# 2_Unextended55_matrix.net
KiCad netlist of a schematic drawn in Altium Designer
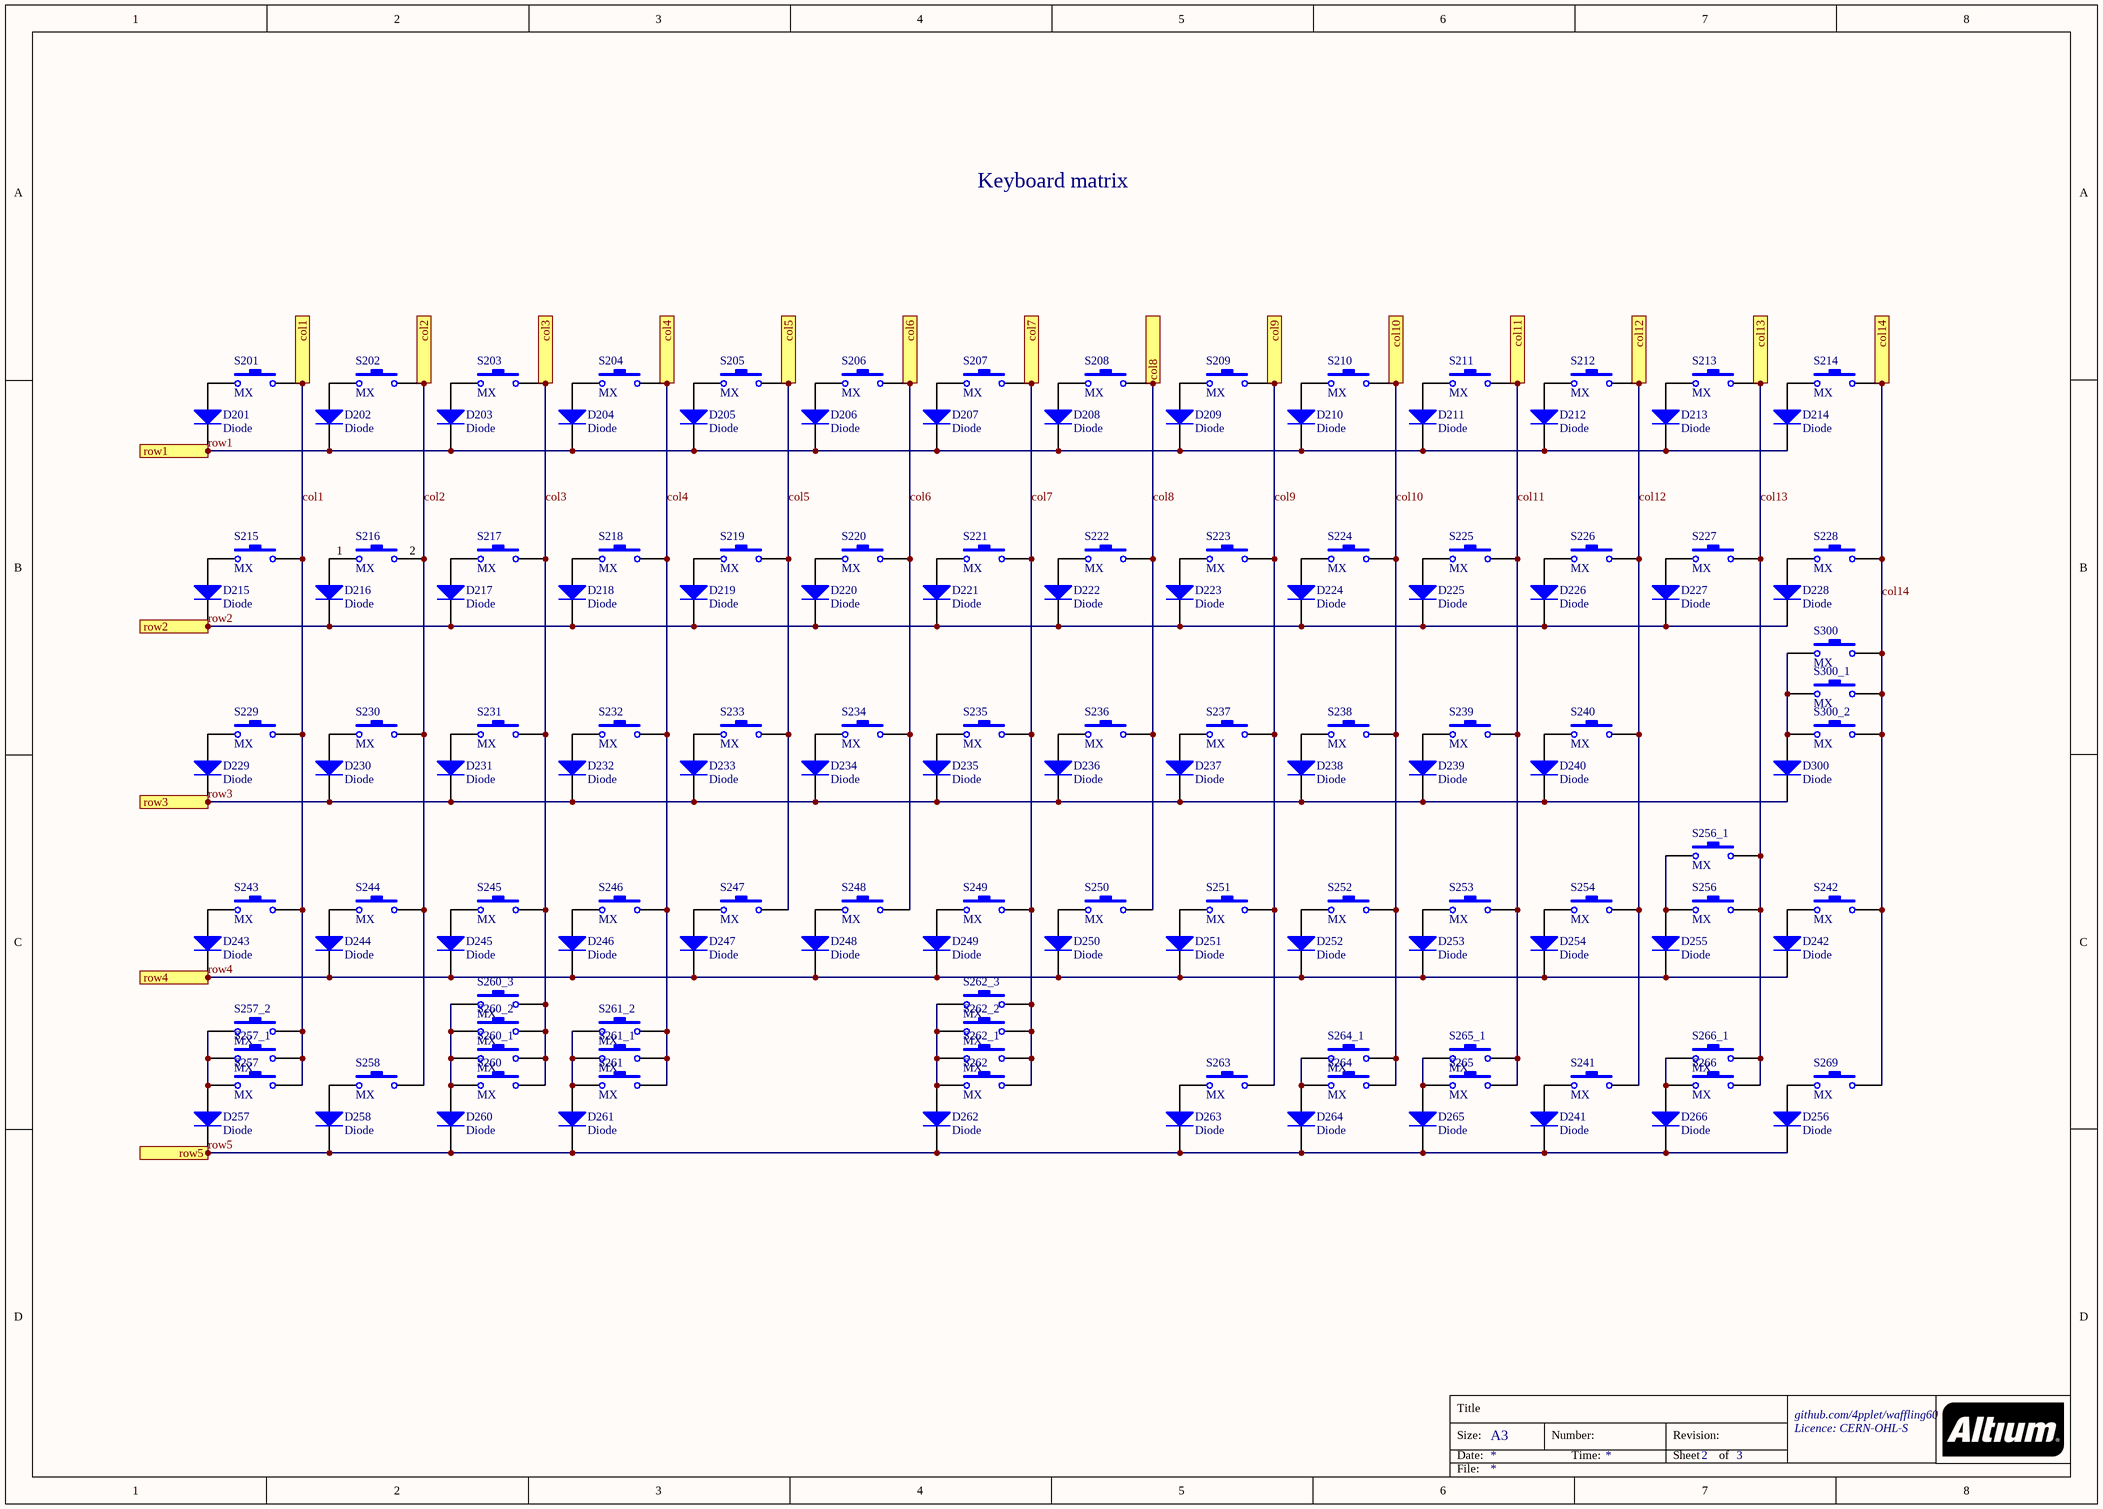
[diagram p0: 2_Unextended55_matrix.SchDoc]

(export (version "E")
  (design (tool "Eeschema 10.0.6"))
  (components
    (comp (ref "D201")
      (value "Diode")
      (footprint "SOD-123")
      (description "Default Diode")
      (fields (field (name "LCSC PART #") "C81598") (field (name "MRF.PART") "1N4148W"))
      (libsource (lib "Miscellaneous Devices") (part "Diode"))
    )
    (comp (ref "D202")
      (value "Diode")
      (footprint "SOD-123")
      (description "Default Diode")
      (fields (field (name "LCSC PART #") "C81598") (field (name "MRF.PART") "1N4148W"))
      (libsource (lib "Miscellaneous Devices") (part "Diode"))
    )
    (comp (ref "D203")
      (value "Diode")
      (footprint "SOD-123")
      (description "Default Diode")
      (fields (field (name "LCSC PART #") "C81598") (field (name "MRF.PART") "1N4148W"))
      (libsource (lib "Miscellaneous Devices") (part "Diode"))
    )
    (comp (ref "D204")
      (value "Diode")
      (footprint "SOD-123")
      (description "Default Diode")
      (fields (field (name "LCSC PART #") "C81598") (field (name "MRF.PART") "1N4148W"))
      (libsource (lib "Miscellaneous Devices") (part "Diode"))
    )
    (comp (ref "D205")
      (value "Diode")
      (footprint "SOD-123")
      (description "Default Diode")
      (fields (field (name "LCSC PART #") "C81598") (field (name "MRF.PART") "1N4148W"))
      (libsource (lib "Miscellaneous Devices") (part "Diode"))
    )
    (comp (ref "D206")
      (value "Diode")
      (footprint "SOD-123")
      (description "Default Diode")
      (fields (field (name "LCSC PART #") "C81598") (field (name "MRF.PART") "1N4148W"))
      (libsource (lib "Miscellaneous Devices") (part "Diode"))
    )
    (comp (ref "D207")
      (value "Diode")
      (footprint "SOD-123")
      (description "Default Diode")
      (fields (field (name "LCSC PART #") "C81598") (field (name "MRF.PART") "1N4148W"))
      (libsource (lib "Miscellaneous Devices") (part "Diode"))
    )
    (comp (ref "D208")
      (value "Diode")
      (footprint "SOD-123")
      (description "Default Diode")
      (fields (field (name "LCSC PART #") "C81598") (field (name "MRF.PART") "1N4148W"))
      (libsource (lib "Miscellaneous Devices") (part "Diode"))
    )
    (comp (ref "D209")
      (value "Diode")
      (footprint "SOD-123")
      (description "Default Diode")
      (fields (field (name "LCSC PART #") "C81598") (field (name "MRF.PART") "1N4148W"))
      (libsource (lib "Miscellaneous Devices") (part "Diode"))
    )
    (comp (ref "D210")
      (value "Diode")
      (footprint "SOD-123")
      (description "Default Diode")
      (fields (field (name "LCSC PART #") "C81598") (field (name "MRF.PART") "1N4148W"))
      (libsource (lib "Miscellaneous Devices") (part "Diode"))
    )
    (comp (ref "D211")
      (value "Diode")
      (footprint "SOD-123")
      (description "Default Diode")
      (fields (field (name "LCSC PART #") "C81598") (field (name "MRF.PART") "1N4148W"))
      (libsource (lib "Miscellaneous Devices") (part "Diode"))
    )
    (comp (ref "D212")
      (value "Diode")
      (footprint "SOD-123")
      (description "Default Diode")
      (fields (field (name "LCSC PART #") "C81598") (field (name "MRF.PART") "1N4148W"))
      (libsource (lib "Miscellaneous Devices") (part "Diode"))
    )
    (comp (ref "D213")
      (value "Diode")
      (footprint "SOD-123")
      (description "Default Diode")
      (fields (field (name "LCSC PART #") "C81598") (field (name "MRF.PART") "1N4148W"))
      (libsource (lib "Miscellaneous Devices") (part "Diode"))
    )
    (comp (ref "D214")
      (value "Diode")
      (footprint "SOD-123")
      (description "Default Diode")
      (fields (field (name "LCSC PART #") "C81598") (field (name "MRF.PART") "1N4148W"))
      (libsource (lib "Miscellaneous Devices") (part "Diode"))
    )
    (comp (ref "D215")
      (value "Diode")
      (footprint "SOD-123")
      (description "Default Diode")
      (fields (field (name "LCSC PART #") "C81598") (field (name "MRF.PART") "1N4148W"))
      (libsource (lib "Miscellaneous Devices") (part "Diode"))
    )
    (comp (ref "D216")
      (value "Diode")
      (footprint "SOD-123")
      (description "Default Diode")
      (fields (field (name "LCSC PART #") "C81598") (field (name "MRF.PART") "1N4148W"))
      (libsource (lib "Miscellaneous Devices") (part "Diode"))
    )
    (comp (ref "D217")
      (value "Diode")
      (footprint "SOD-123")
      (description "Default Diode")
      (fields (field (name "LCSC PART #") "C81598") (field (name "MRF.PART") "1N4148W"))
      (libsource (lib "Miscellaneous Devices") (part "Diode"))
    )
    (comp (ref "D218")
      (value "Diode")
      (footprint "SOD-123")
      (description "Default Diode")
      (fields (field (name "LCSC PART #") "C81598") (field (name "MRF.PART") "1N4148W"))
      (libsource (lib "Miscellaneous Devices") (part "Diode"))
    )
    (comp (ref "D219")
      (value "Diode")
      (footprint "SOD-123")
      (description "Default Diode")
      (fields (field (name "LCSC PART #") "C81598") (field (name "MRF.PART") "1N4148W"))
      (libsource (lib "Miscellaneous Devices") (part "Diode"))
    )
    (comp (ref "D220")
      (value "Diode")
      (footprint "SOD-123")
      (description "Default Diode")
      (fields (field (name "LCSC PART #") "C81598") (field (name "MRF.PART") "1N4148W"))
      (libsource (lib "Miscellaneous Devices") (part "Diode"))
    )
    (comp (ref "D221")
      (value "Diode")
      (footprint "SOD-123")
      (description "Default Diode")
      (fields (field (name "LCSC PART #") "C81598") (field (name "MRF.PART") "1N4148W"))
      (libsource (lib "Miscellaneous Devices") (part "Diode"))
    )
    (comp (ref "D222")
      (value "Diode")
      (footprint "SOD-123")
      (description "Default Diode")
      (fields (field (name "LCSC PART #") "C81598") (field (name "MRF.PART") "1N4148W"))
      (libsource (lib "Miscellaneous Devices") (part "Diode"))
    )
    (comp (ref "D223")
      (value "Diode")
      (footprint "SOD-123")
      (description "Default Diode")
      (fields (field (name "LCSC PART #") "C81598") (field (name "MRF.PART") "1N4148W"))
      (libsource (lib "Miscellaneous Devices") (part "Diode"))
    )
    (comp (ref "D224")
      (value "Diode")
      (footprint "SOD-123")
      (description "Default Diode")
      (fields (field (name "LCSC PART #") "C81598") (field (name "MRF.PART") "1N4148W"))
      (libsource (lib "Miscellaneous Devices") (part "Diode"))
    )
    (comp (ref "D225")
      (value "Diode")
      (footprint "SOD-123")
      (description "Default Diode")
      (fields (field (name "LCSC PART #") "C81598") (field (name "MRF.PART") "1N4148W"))
      (libsource (lib "Miscellaneous Devices") (part "Diode"))
    )
    (comp (ref "D226")
      (value "Diode")
      (footprint "SOD-123")
      (description "Default Diode")
      (fields (field (name "LCSC PART #") "C81598") (field (name "MRF.PART") "1N4148W"))
      (libsource (lib "Miscellaneous Devices") (part "Diode"))
    )
    (comp (ref "D227")
      (value "Diode")
      (footprint "SOD-123")
      (description "Default Diode")
      (fields (field (name "LCSC PART #") "C81598") (field (name "MRF.PART") "1N4148W"))
      (libsource (lib "Miscellaneous Devices") (part "Diode"))
    )
    (comp (ref "D228")
      (value "Diode")
      (footprint "SOD-123")
      (description "Default Diode")
      (fields (field (name "LCSC PART #") "C81598") (field (name "MRF.PART") "1N4148W"))
      (libsource (lib "Miscellaneous Devices") (part "Diode"))
    )
    (comp (ref "D229")
      (value "Diode")
      (footprint "SOD-123")
      (description "Default Diode")
      (fields (field (name "LCSC PART #") "C81598") (field (name "MRF.PART") "1N4148W"))
      (libsource (lib "Miscellaneous Devices") (part "Diode"))
    )
    (comp (ref "D230")
      (value "Diode")
      (footprint "SOD-123")
      (description "Default Diode")
      (fields (field (name "LCSC PART #") "C81598") (field (name "MRF.PART") "1N4148W"))
      (libsource (lib "Miscellaneous Devices") (part "Diode"))
    )
    (comp (ref "D231")
      (value "Diode")
      (footprint "SOD-123")
      (description "Default Diode")
      (fields (field (name "LCSC PART #") "C81598") (field (name "MRF.PART") "1N4148W"))
      (libsource (lib "Miscellaneous Devices") (part "Diode"))
    )
    (comp (ref "D232")
      (value "Diode")
      (footprint "SOD-123")
      (description "Default Diode")
      (fields (field (name "LCSC PART #") "C81598") (field (name "MRF.PART") "1N4148W"))
      (libsource (lib "Miscellaneous Devices") (part "Diode"))
    )
    (comp (ref "D233")
      (value "Diode")
      (footprint "SOD-123")
      (description "Default Diode")
      (fields (field (name "LCSC PART #") "C81598") (field (name "MRF.PART") "1N4148W"))
      (libsource (lib "Miscellaneous Devices") (part "Diode"))
    )
    (comp (ref "D234")
      (value "Diode")
      (footprint "SOD-123")
      (description "Default Diode")
      (fields (field (name "LCSC PART #") "C81598") (field (name "MRF.PART") "1N4148W"))
      (libsource (lib "Miscellaneous Devices") (part "Diode"))
    )
    (comp (ref "D235")
      (value "Diode")
      (footprint "SOD-123")
      (description "Default Diode")
      (fields (field (name "LCSC PART #") "C81598") (field (name "MRF.PART") "1N4148W"))
      (libsource (lib "Miscellaneous Devices") (part "Diode"))
    )
    (comp (ref "D236")
      (value "Diode")
      (footprint "SOD-123")
      (description "Default Diode")
      (fields (field (name "LCSC PART #") "C81598") (field (name "MRF.PART") "1N4148W"))
      (libsource (lib "Miscellaneous Devices") (part "Diode"))
    )
    (comp (ref "D237")
      (value "Diode")
      (footprint "SOD-123")
      (description "Default Diode")
      (fields (field (name "LCSC PART #") "C81598") (field (name "MRF.PART") "1N4148W"))
      (libsource (lib "Miscellaneous Devices") (part "Diode"))
    )
    (comp (ref "D238")
      (value "Diode")
      (footprint "SOD-123")
      (description "Default Diode")
      (fields (field (name "LCSC PART #") "C81598") (field (name "MRF.PART") "1N4148W"))
      (libsource (lib "Miscellaneous Devices") (part "Diode"))
    )
    (comp (ref "D239")
      (value "Diode")
      (footprint "SOD-123")
      (description "Default Diode")
      (fields (field (name "LCSC PART #") "C81598") (field (name "MRF.PART") "1N4148W"))
      (libsource (lib "Miscellaneous Devices") (part "Diode"))
    )
    (comp (ref "D240")
      (value "Diode")
      (footprint "SOD-123")
      (description "Default Diode")
      (fields (field (name "LCSC PART #") "C81598") (field (name "MRF.PART") "1N4148W"))
      (libsource (lib "Miscellaneous Devices") (part "Diode"))
    )
    (comp (ref "D241")
      (value "Diode")
      (footprint "SOD-123")
      (description "Default Diode")
      (fields (field (name "LCSC PART #") "C81598") (field (name "MRF.PART") "1N4148W"))
      (libsource (lib "Miscellaneous Devices") (part "Diode"))
    )
    (comp (ref "D242")
      (value "Diode")
      (footprint "SOD-123")
      (description "Default Diode")
      (fields (field (name "LCSC PART #") "C81598") (field (name "MRF.PART") "1N4148W"))
      (libsource (lib "Miscellaneous Devices") (part "Diode"))
    )
    (comp (ref "D243")
      (value "Diode")
      (footprint "SOD-123")
      (description "Default Diode")
      (fields (field (name "LCSC PART #") "C81598") (field (name "MRF.PART") "1N4148W"))
      (libsource (lib "Miscellaneous Devices") (part "Diode"))
    )
    (comp (ref "D244")
      (value "Diode")
      (footprint "SOD-123")
      (description "Default Diode")
      (fields (field (name "LCSC PART #") "C81598") (field (name "MRF.PART") "1N4148W"))
      (libsource (lib "Miscellaneous Devices") (part "Diode"))
    )
    (comp (ref "D245")
      (value "Diode")
      (footprint "SOD-123")
      (description "Default Diode")
      (fields (field (name "LCSC PART #") "C81598") (field (name "MRF.PART") "1N4148W"))
      (libsource (lib "Miscellaneous Devices") (part "Diode"))
    )
    (comp (ref "D246")
      (value "Diode")
      (footprint "SOD-123")
      (description "Default Diode")
      (fields (field (name "LCSC PART #") "C81598") (field (name "MRF.PART") "1N4148W"))
      (libsource (lib "Miscellaneous Devices") (part "Diode"))
    )
    (comp (ref "D247")
      (value "Diode")
      (footprint "SOD-123")
      (description "Default Diode")
      (fields (field (name "LCSC PART #") "C81598") (field (name "MRF.PART") "1N4148W"))
      (libsource (lib "Miscellaneous Devices") (part "Diode"))
    )
    (comp (ref "D248")
      (value "Diode")
      (footprint "SOD-123")
      (description "Default Diode")
      (fields (field (name "LCSC PART #") "C81598") (field (name "MRF.PART") "1N4148W"))
      (libsource (lib "Miscellaneous Devices") (part "Diode"))
    )
    (comp (ref "D249")
      (value "Diode")
      (footprint "SOD-123")
      (description "Default Diode")
      (fields (field (name "LCSC PART #") "C81598") (field (name "MRF.PART") "1N4148W"))
      (libsource (lib "Miscellaneous Devices") (part "Diode"))
    )
    (comp (ref "D250")
      (value "Diode")
      (footprint "SOD-123")
      (description "Default Diode")
      (fields (field (name "LCSC PART #") "C81598") (field (name "MRF.PART") "1N4148W"))
      (libsource (lib "Miscellaneous Devices") (part "Diode"))
    )
    (comp (ref "D251")
      (value "Diode")
      (footprint "SOD-123")
      (description "Default Diode")
      (fields (field (name "LCSC PART #") "C81598") (field (name "MRF.PART") "1N4148W"))
      (libsource (lib "Miscellaneous Devices") (part "Diode"))
    )
    (comp (ref "D252")
      (value "Diode")
      (footprint "SOD-123")
      (description "Default Diode")
      (fields (field (name "LCSC PART #") "C81598") (field (name "MRF.PART") "1N4148W"))
      (libsource (lib "Miscellaneous Devices") (part "Diode"))
    )
    (comp (ref "D253")
      (value "Diode")
      (footprint "SOD-123")
      (description "Default Diode")
      (fields (field (name "LCSC PART #") "C81598") (field (name "MRF.PART") "1N4148W"))
      (libsource (lib "Miscellaneous Devices") (part "Diode"))
    )
    (comp (ref "D254")
      (value "Diode")
      (footprint "SOD-123")
      (description "Default Diode")
      (fields (field (name "LCSC PART #") "C81598") (field (name "MRF.PART") "1N4148W"))
      (libsource (lib "Miscellaneous Devices") (part "Diode"))
    )
    (comp (ref "D255")
      (value "Diode")
      (footprint "SOD-123")
      (description "Default Diode")
      (fields (field (name "LCSC PART #") "C81598") (field (name "MRF.PART") "1N4148W"))
      (libsource (lib "Miscellaneous Devices") (part "Diode"))
    )
    (comp (ref "D256")
      (value "Diode")
      (footprint "SOD-123")
      (description "Default Diode")
      (fields (field (name "LCSC PART #") "C81598") (field (name "MRF.PART") "1N4148W"))
      (libsource (lib "Miscellaneous Devices") (part "Diode"))
    )
    (comp (ref "D257")
      (value "Diode")
      (footprint "SOD-123")
      (description "Default Diode")
      (fields (field (name "LCSC PART #") "C81598") (field (name "MRF.PART") "1N4148W"))
      (libsource (lib "Miscellaneous Devices") (part "Diode"))
    )
    (comp (ref "D258")
      (value "Diode")
      (footprint "SOD-123")
      (description "Default Diode")
      (fields (field (name "LCSC PART #") "C81598") (field (name "MRF.PART") "1N4148W"))
      (libsource (lib "Miscellaneous Devices") (part "Diode"))
    )
    (comp (ref "D260")
      (value "Diode")
      (footprint "SOD-123")
      (description "Default Diode")
      (fields (field (name "LCSC PART #") "C81598") (field (name "MRF.PART") "1N4148W"))
      (libsource (lib "Miscellaneous Devices") (part "Diode"))
    )
    (comp (ref "D261")
      (value "Diode")
      (footprint "SOD-123")
      (description "Default Diode")
      (fields (field (name "LCSC PART #") "C81598") (field (name "MRF.PART") "1N4148W"))
      (libsource (lib "Miscellaneous Devices") (part "Diode"))
    )
    (comp (ref "D262")
      (value "Diode")
      (footprint "SOD-123")
      (description "Default Diode")
      (fields (field (name "LCSC PART #") "C81598") (field (name "MRF.PART") "1N4148W"))
      (libsource (lib "Miscellaneous Devices") (part "Diode"))
    )
    (comp (ref "D263")
      (value "Diode")
      (footprint "SOD-123")
      (description "Default Diode")
      (fields (field (name "LCSC PART #") "C81598") (field (name "MRF.PART") "1N4148W"))
      (libsource (lib "Miscellaneous Devices") (part "Diode"))
    )
    (comp (ref "D264")
      (value "Diode")
      (footprint "SOD-123")
      (description "Default Diode")
      (fields (field (name "LCSC PART #") "C81598") (field (name "MRF.PART") "1N4148W"))
      (libsource (lib "Miscellaneous Devices") (part "Diode"))
    )
    (comp (ref "D265")
      (value "Diode")
      (footprint "SOD-123")
      (description "Default Diode")
      (fields (field (name "LCSC PART #") "C81598") (field (name "MRF.PART") "1N4148W"))
      (libsource (lib "Miscellaneous Devices") (part "Diode"))
    )
    (comp (ref "D266")
      (value "Diode")
      (footprint "SOD-123")
      (description "Default Diode")
      (fields (field (name "LCSC PART #") "C81598") (field (name "MRF.PART") "1N4148W"))
      (libsource (lib "Miscellaneous Devices") (part "Diode"))
    )
    (comp (ref "D300")
      (value "Diode")
      (footprint "SOD-123")
      (description "Default Diode")
      (fields (field (name "LCSC PART #") "C81598") (field (name "MRF.PART") "1N4148W"))
      (libsource (lib "Miscellaneous Devices") (part "Diode"))
    )
    (comp (ref "S201")
      (value "MX")
      (footprint "Alps-switch - switched pol")
      (description "Switch")
      (libsource (lib "Miscellaneous Devices") (part "SW-PB"))
    )
    (comp (ref "S202")
      (value "MX")
      (footprint "Alps-switch - switched pol")
      (description "Switch")
      (libsource (lib "Miscellaneous Devices") (part "SW-PB"))
    )
    (comp (ref "S203")
      (value "MX")
      (footprint "Alps-switch - switched pol")
      (description "Switch")
      (libsource (lib "Miscellaneous Devices") (part "SW-PB"))
    )
    (comp (ref "S204")
      (value "MX")
      (footprint "Alps-switch - switched pol")
      (description "Switch")
      (libsource (lib "Miscellaneous Devices") (part "SW-PB"))
    )
    (comp (ref "S205")
      (value "MX")
      (footprint "Alps-switch - switched pol")
      (description "Switch")
      (libsource (lib "Miscellaneous Devices") (part "SW-PB"))
    )
    (comp (ref "S206")
      (value "MX")
      (footprint "Alps-switch - switched pol")
      (description "Switch")
      (libsource (lib "Miscellaneous Devices") (part "SW-PB"))
    )
    (comp (ref "S207")
      (value "MX")
      (footprint "Alps-switch - switched pol")
      (description "Switch")
      (libsource (lib "Miscellaneous Devices") (part "SW-PB"))
    )
    (comp (ref "S208")
      (value "MX")
      (footprint "Alps-switch - switched pol")
      (description "Switch")
      (libsource (lib "Miscellaneous Devices") (part "SW-PB"))
    )
    (comp (ref "S209")
      (value "MX")
      (footprint "Alps-switch - switched pol")
      (description "Switch")
      (libsource (lib "Miscellaneous Devices") (part "SW-PB"))
    )
    (comp (ref "S210")
      (value "MX")
      (footprint "Alps-switch - switched pol")
      (description "Switch")
      (libsource (lib "Miscellaneous Devices") (part "SW-PB"))
    )
    (comp (ref "S211")
      (value "MX")
      (footprint "Alps-switch - switched pol")
      (description "Switch")
      (libsource (lib "Miscellaneous Devices") (part "SW-PB"))
    )
    (comp (ref "S212")
      (value "MX")
      (footprint "Alps-switch - switched pol")
      (description "Switch")
      (libsource (lib "Miscellaneous Devices") (part "SW-PB"))
    )
    (comp (ref "S213")
      (value "MX")
      (footprint "Alps-switch - switched pol")
      (description "Switch")
      (libsource (lib "Miscellaneous Devices") (part "SW-PB"))
    )
    (comp (ref "S214")
      (value "MX")
      (footprint "ALPS-switch - 1.5U")
      (description "Switch")
      (libsource (lib "Miscellaneous Devices") (part "SW-PB"))
    )
    (comp (ref "S215")
      (value "MX")
      (footprint "Alps-switch - switched pol")
      (description "TAB")
      (libsource (lib "Miscellaneous Devices") (part "SW-PB"))
    )
    (comp (ref "S216")
      (value "MX")
      (footprint "Alps-switch")
      (description "Switch")
      (libsource (lib "") (part "SW-PB_1"))
    )
    (comp (ref "S217")
      (value "MX")
      (footprint "Alps-switch - switched pol")
      (description "Switch")
      (libsource (lib "Miscellaneous Devices") (part "SW-PB"))
    )
    (comp (ref "S218")
      (value "MX")
      (footprint "Alps-switch - switched pol")
      (description "Switch")
      (libsource (lib "Miscellaneous Devices") (part "SW-PB"))
    )
    (comp (ref "S219")
      (value "MX")
      (footprint "Alps-switch - switched pol")
      (description "Switch")
      (libsource (lib "Miscellaneous Devices") (part "SW-PB"))
    )
    (comp (ref "S220")
      (value "MX")
      (footprint "Alps-switch - switched pol")
      (description "Switch")
      (libsource (lib "Miscellaneous Devices") (part "SW-PB"))
    )
    (comp (ref "S221")
      (value "MX")
      (footprint "Alps-switch - switched pol")
      (description "Switch")
      (libsource (lib "Miscellaneous Devices") (part "SW-PB"))
    )
    (comp (ref "S222")
      (value "MX")
      (footprint "Alps-switch - switched pol")
      (description "Switch")
      (libsource (lib "Miscellaneous Devices") (part "SW-PB"))
    )
    (comp (ref "S223")
      (value "MX")
      (footprint "Alps-switch - switched pol")
      (description "Switch")
      (libsource (lib "Miscellaneous Devices") (part "SW-PB"))
    )
    (comp (ref "S224")
      (value "MX")
      (footprint "Alps-switch - switched pol")
      (description "Switch")
      (libsource (lib "Miscellaneous Devices") (part "SW-PB"))
    )
    (comp (ref "S225")
      (value "MX")
      (footprint "Alps-switch - switched pol")
      (description "Switch")
      (libsource (lib "Miscellaneous Devices") (part "SW-PB"))
    )
    (comp (ref "S226")
      (value "MX")
      (footprint "Alps-switch")
      (description "Switch")
      (libsource (lib "Miscellaneous Devices") (part "SW-PB"))
    )
    (comp (ref "S227")
      (value "MX")
      (footprint "Alps-switch")
      (description "Switch")
      (libsource (lib "Miscellaneous Devices") (part "SW-PB"))
    )
    (comp (ref "S228")
      (value "MX")
      (footprint "Alps-switch - switched pol")
      (description "Switch")
      (libsource (lib "Miscellaneous Devices") (part "SW-PB"))
    )
    (comp (ref "S229")
      (value "MX")
      (footprint "Alps-switch - switched pol")
      (description "Switch")
      (libsource (lib "Miscellaneous Devices") (part "SW-PB"))
    )
    (comp (ref "S230")
      (value "MX")
      (footprint "Alps-switch")
      (description "Switch")
      (libsource (lib "Miscellaneous Devices") (part "SW-PB"))
    )
    (comp (ref "S231")
      (value "MX")
      (footprint "Alps-switch - switched pol")
      (description "Switch")
      (libsource (lib "Miscellaneous Devices") (part "SW-PB"))
    )
    (comp (ref "S232")
      (value "MX")
      (footprint "Alps-switch - switched pol")
      (description "Switch")
      (libsource (lib "Miscellaneous Devices") (part "SW-PB"))
    )
    (comp (ref "S233")
      (value "MX")
      (footprint "Alps-switch - switched pol")
      (description "Switch")
      (libsource (lib "Miscellaneous Devices") (part "SW-PB"))
    )
    (comp (ref "S234")
      (value "MX")
      (footprint "Alps-switch - switched pol")
      (description "Switch")
      (libsource (lib "Miscellaneous Devices") (part "SW-PB"))
    )
    (comp (ref "S235")
      (value "MX")
      (footprint "Alps-switch - switched pol")
      (description "Switch")
      (libsource (lib "Miscellaneous Devices") (part "SW-PB"))
    )
    (comp (ref "S236")
      (value "MX")
      (footprint "Alps-switch - switched pol")
      (description "Switch")
      (libsource (lib "Miscellaneous Devices") (part "SW-PB"))
    )
    (comp (ref "S237")
      (value "MX")
      (footprint "Alps-switch - switched pol")
      (description "Switch")
      (libsource (lib "Miscellaneous Devices") (part "SW-PB"))
    )
    (comp (ref "S238")
      (value "MX")
      (footprint "Alps-switch - switched pol")
      (description "Switch")
      (libsource (lib "Miscellaneous Devices") (part "SW-PB"))
    )
    (comp (ref "S239")
      (value "MX")
      (footprint "Alps-switch - switched pol")
      (description "Switch")
      (libsource (lib "Miscellaneous Devices") (part "SW-PB"))
    )
    (comp (ref "S240")
      (value "MX")
      (footprint "Alps-switch - switched pol")
      (description "Switch")
      (libsource (lib "Miscellaneous Devices") (part "SW-PB"))
    )
    (comp (ref "S241")
      (value "MX")
      (footprint "Alps-switch")
      (description "Switch")
      (libsource (lib "Miscellaneous Devices") (part "SW-PB"))
    )
    (comp (ref "S242")
      (value "MX")
      (footprint "Alps-switch")
      (description "Switch")
      (libsource (lib "Miscellaneous Devices") (part "SW-PB"))
    )
    (comp (ref "S243")
      (value "MX")
      (footprint "ALPS-switch - Left shift v2")
      (description "Switch")
      (libsource (lib "Miscellaneous Devices") (part "SW-PB"))
    )
    (comp (ref "S244")
      (value "MX")
      (footprint "Alps-switch")
      (description "Switch")
      (libsource (lib "Miscellaneous Devices") (part "SW-PB"))
    )
    (comp (ref "S245")
      (value "MX")
      (footprint "Alps-switch - switched pol")
      (description "Switch")
      (libsource (lib "Miscellaneous Devices") (part "SW-PB"))
    )
    (comp (ref "S246")
      (value "MX")
      (footprint "Alps-switch - switched pol")
      (description "Switch")
      (libsource (lib "Miscellaneous Devices") (part "SW-PB"))
    )
    (comp (ref "S247")
      (value "MX")
      (footprint "Alps-switch - switched pol")
      (description "Switch")
      (libsource (lib "Miscellaneous Devices") (part "SW-PB"))
    )
    (comp (ref "S248")
      (value "MX")
      (footprint "Alps-switch - switched pol")
      (description "Switch")
      (libsource (lib "Miscellaneous Devices") (part "SW-PB"))
    )
    (comp (ref "S249")
      (value "MX")
      (footprint "Alps-switch - switched pol")
      (description "Switch")
      (libsource (lib "Miscellaneous Devices") (part "SW-PB"))
    )
    (comp (ref "S250")
      (value "MX")
      (footprint "Alps-switch - switched pol")
      (description "Switch")
      (libsource (lib "Miscellaneous Devices") (part "SW-PB"))
    )
    (comp (ref "S251")
      (value "MX")
      (footprint "Alps-switch - switched pol")
      (description "Switch")
      (libsource (lib "Miscellaneous Devices") (part "SW-PB"))
    )
    (comp (ref "S252")
      (value "MX")
      (footprint "Alps-switch - switched pol")
      (description "Switch")
      (libsource (lib "Miscellaneous Devices") (part "SW-PB"))
    )
    (comp (ref "S253")
      (value "MX")
      (footprint "Alps-switch - switched pol")
      (description "Switch")
      (libsource (lib "Miscellaneous Devices") (part "SW-PB"))
    )
    (comp (ref "S254")
      (value "MX")
      (footprint "Alps-switch - switched pol")
      (description "Switch")
      (libsource (lib "Miscellaneous Devices") (part "SW-PB"))
    )
    (comp (ref "S256")
      (value "MX")
      (footprint "ALPS-switch - 2.25U")
      (description "Switch")
      (libsource (lib "Miscellaneous Devices") (part "SW-PB"))
    )
    (comp (ref "S256_1")
      (value "MX")
      (footprint "Alps-switch - switched pol")
      (description "Switch")
      (libsource (lib "Miscellaneous Devices") (part "SW-PB"))
    )
    (comp (ref "S257")
      (value "MX")
      (footprint "Alps-switch - switched pol")
      (description "Switch")
      (libsource (lib "Miscellaneous Devices") (part "SW-PB"))
    )
    (comp (ref "S257_1")
      (value "MX")
      (footprint "Alps-switch")
      (description "Switch")
      (libsource (lib "Miscellaneous Devices") (part "SW-PB"))
    )
    (comp (ref "S257_2")
      (value "MX")
      (footprint "Alps-switch")
      (description "Switch")
      (libsource (lib "Miscellaneous Devices") (part "SW-PB"))
    )
    (comp (ref "S258")
      (value "MX")
      (footprint "Alps-switch")
      (description "Switch")
      (libsource (lib "Miscellaneous Devices") (part "SW-PB"))
    )
    (comp (ref "S260")
      (value "MX")
      (footprint "Alps-switch")
      (description "Switch")
      (libsource (lib "Miscellaneous Devices") (part "SW-PB"))
    )
    (comp (ref "S260_1")
      (value "MX")
      (footprint "Alps-switch - switched pol")
      (description "Switch")
      (libsource (lib "Miscellaneous Devices") (part "SW-PB"))
    )
    (comp (ref "S260_2")
      (value "MX")
      (footprint "Alps-switch")
      (description "Switch")
      (libsource (lib "Miscellaneous Devices") (part "SW-PB"))
    )
    (comp (ref "S260_3")
      (value "MX")
      (footprint "Alps-switch - switched pol")
      (description "Switch")
      (libsource (lib "Miscellaneous Devices") (part "SW-PB"))
    )
    (comp (ref "S261")
      (value "MX")
      (footprint "Alps-switch")
      (description "Switch")
      (libsource (lib "Miscellaneous Devices") (part "SW-PB"))
    )
    (comp (ref "S261_1")
      (value "MX")
      (footprint "Alps-switch - switched pol")
      (description "Switch")
      (libsource (lib "Miscellaneous Devices") (part "SW-PB"))
    )
    (comp (ref "S261_2")
      (value "MX")
      (footprint "Alps-switch - switched pol")
      (description "Switch")
      (libsource (lib "Miscellaneous Devices") (part "SW-PB"))
    )
    (comp (ref "S262")
      (value "MX")
      (footprint "Alps-switch")
      (description "Switch")
      (libsource (lib "Miscellaneous Devices") (part "SW-PB"))
    )
    (comp (ref "S262_1")
      (value "MX")
      (footprint "Alps-switch")
      (description "Switch")
      (libsource (lib "Miscellaneous Devices") (part "SW-PB"))
    )
    (comp (ref "S262_2")
      (value "MX")
      (footprint "Alps-switch - switched pol")
      (description "Switch")
      (libsource (lib "Miscellaneous Devices") (part "SW-PB"))
    )
    (comp (ref "S262_3")
      (value "MX")
      (footprint "Alps-switch")
      (description "Switch")
      (libsource (lib "Miscellaneous Devices") (part "SW-PB"))
    )
    (comp (ref "S263")
      (value "MX")
      (footprint "Alps-switch")
      (description "Switch")
      (libsource (lib "Miscellaneous Devices") (part "SW-PB"))
    )
    (comp (ref "S264")
      (value "MX")
      (footprint "Alps-switch - switched pol")
      (description "Switch")
      (libsource (lib "Miscellaneous Devices") (part "SW-PB"))
    )
    (comp (ref "S264_1")
      (value "MX")
      (footprint "Alps-switch")
      (description "Switch")
      (libsource (lib "Miscellaneous Devices") (part "SW-PB"))
    )
    (comp (ref "S265")
      (value "MX")
      (footprint "Alps-switch - switched pol")
      (description "Switch")
      (libsource (lib "Miscellaneous Devices") (part "SW-PB"))
    )
    (comp (ref "S265_1")
      (value "MX")
      (footprint "Alps-switch")
      (description "Switch")
      (libsource (lib "Miscellaneous Devices") (part "SW-PB"))
    )
    (comp (ref "S266")
      (value "MX")
      (footprint "Alps-switch - switched pol")
      (description "Switch")
      (libsource (lib "Miscellaneous Devices") (part "SW-PB"))
    )
    (comp (ref "S266_1")
      (value "MX")
      (footprint "Alps-switch")
      (description "Switch")
      (libsource (lib "Miscellaneous Devices") (part "SW-PB"))
    )
    (comp (ref "S269")
      (value "MX")
      (footprint "Alps-switch")
      (description "Switch")
      (libsource (lib "Miscellaneous Devices") (part "SW-PB"))
    )
    (comp (ref "S300")
      (value "MX")
      (footprint "Alps-switch")
      (description "Switch")
      (libsource (lib "Miscellaneous Devices") (part "SW-PB"))
    )
    (comp (ref "S300_1")
      (value "MX")
      (footprint "Alps-switch")
      (description "Switch")
      (libsource (lib "Miscellaneous Devices") (part "SW-PB"))
    )
    (comp (ref "S300_2")
      (value "MX")
      (footprint "Alps-switch - switched pol")
      (description "Switch")
      (libsource (lib "Miscellaneous Devices") (part "SW-PB"))
    )
  )
  (nets
    (net (code "1") (name "/col1") (class "Default")
      (node (ref "S201") (pin "2") (pinfunction "2_2") (pintype "passive"))
      (node (ref "S215") (pin "2") (pinfunction "2_2") (pintype "passive"))
      (node (ref "S229") (pin "2") (pinfunction "2_2") (pintype "passive"))
      (node (ref "S243") (pin "2") (pinfunction "2_2") (pintype "passive"))
      (node (ref "S257") (pin "1") (pinfunction "1_1") (pintype "passive"))
      (node (ref "S257_1") (pin "1") (pinfunction "1_1") (pintype "passive"))
      (node (ref "S257_2") (pin "1") (pinfunction "1_1") (pintype "passive"))
    )
    (net (code "2") (name "/col2") (class "Default")
      (node (ref "S202") (pin "2") (pinfunction "2_2") (pintype "passive"))
      (node (ref "S216") (pin "2") (pinfunction "2_2") (pintype "passive"))
      (node (ref "S230") (pin "2") (pinfunction "2_2") (pintype "passive"))
      (node (ref "S244") (pin "1") (pinfunction "1_1") (pintype "passive"))
      (node (ref "S258") (pin "2") (pinfunction "2_2") (pintype "passive"))
    )
    (net (code "3") (name "/col3") (class "Default")
      (node (ref "S203") (pin "2") (pinfunction "2_2") (pintype "passive"))
      (node (ref "S217") (pin "2") (pinfunction "2_2") (pintype "passive"))
      (node (ref "S231") (pin "2") (pinfunction "2_2") (pintype "passive"))
      (node (ref "S245") (pin "2") (pinfunction "2_2") (pintype "passive"))
      (node (ref "S260") (pin "2") (pinfunction "2_2") (pintype "passive"))
      (node (ref "S260_1") (pin "2") (pinfunction "2_2") (pintype "passive"))
      (node (ref "S260_2") (pin "2") (pinfunction "2_2") (pintype "passive"))
      (node (ref "S260_3") (pin "2") (pinfunction "2_2") (pintype "passive"))
    )
    (net (code "4") (name "/col4") (class "Default")
      (node (ref "S204") (pin "2") (pinfunction "2_2") (pintype "passive"))
      (node (ref "S218") (pin "2") (pinfunction "2_2") (pintype "passive"))
      (node (ref "S232") (pin "2") (pinfunction "2_2") (pintype "passive"))
      (node (ref "S246") (pin "2") (pinfunction "2_2") (pintype "passive"))
      (node (ref "S261") (pin "2") (pinfunction "2_2") (pintype "passive"))
      (node (ref "S261_1") (pin "2") (pinfunction "2_2") (pintype "passive"))
      (node (ref "S261_2") (pin "2") (pinfunction "2_2") (pintype "passive"))
    )
    (net (code "5") (name "/col5") (class "Default")
      (node (ref "S205") (pin "2") (pinfunction "2_2") (pintype "passive"))
      (node (ref "S219") (pin "2") (pinfunction "2_2") (pintype "passive"))
      (node (ref "S233") (pin "2") (pinfunction "2_2") (pintype "passive"))
      (node (ref "S247") (pin "2") (pinfunction "2_2") (pintype "passive"))
    )
    (net (code "6") (name "/col6") (class "Default")
      (node (ref "S206") (pin "2") (pinfunction "2_2") (pintype "passive"))
      (node (ref "S220") (pin "2") (pinfunction "2_2") (pintype "passive"))
      (node (ref "S234") (pin "2") (pinfunction "2_2") (pintype "passive"))
      (node (ref "S248") (pin "2") (pinfunction "2_2") (pintype "passive"))
    )
    (net (code "7") (name "/col7") (class "Default")
      (node (ref "S207") (pin "2") (pinfunction "2_2") (pintype "passive"))
      (node (ref "S221") (pin "2") (pinfunction "2_2") (pintype "passive"))
      (node (ref "S235") (pin "2") (pinfunction "2_2") (pintype "passive"))
      (node (ref "S249") (pin "2") (pinfunction "2_2") (pintype "passive"))
      (node (ref "S262") (pin "1") (pinfunction "1_1") (pintype "passive"))
      (node (ref "S262_1") (pin "1") (pinfunction "1_1") (pintype "passive"))
      (node (ref "S262_2") (pin "1") (pinfunction "1_1") (pintype "passive"))
      (node (ref "S262_3") (pin "1") (pinfunction "1_1") (pintype "passive"))
    )
    (net (code "8") (name "/col8") (class "Default")
      (node (ref "S208") (pin "2") (pinfunction "2_2") (pintype "passive"))
      (node (ref "S222") (pin "2") (pinfunction "2_2") (pintype "passive"))
      (node (ref "S236") (pin "2") (pinfunction "2_2") (pintype "passive"))
      (node (ref "S250") (pin "2") (pinfunction "2_2") (pintype "passive"))
    )
    (net (code "9") (name "/col9") (class "Default")
      (node (ref "S209") (pin "2") (pinfunction "2_2") (pintype "passive"))
      (node (ref "S223") (pin "2") (pinfunction "2_2") (pintype "passive"))
      (node (ref "S237") (pin "2") (pinfunction "2_2") (pintype "passive"))
      (node (ref "S251") (pin "2") (pinfunction "2_2") (pintype "passive"))
      (node (ref "S263") (pin "1") (pinfunction "1_1") (pintype "passive"))
    )
    (net (code "10") (name "/col10") (class "Default")
      (node (ref "S210") (pin "2") (pinfunction "2_2") (pintype "passive"))
      (node (ref "S224") (pin "2") (pinfunction "2_2") (pintype "passive"))
      (node (ref "S238") (pin "2") (pinfunction "2_2") (pintype "passive"))
      (node (ref "S252") (pin "2") (pinfunction "2_2") (pintype "passive"))
      (node (ref "S264") (pin "2") (pinfunction "2_2") (pintype "passive"))
      (node (ref "S264_1") (pin "2") (pinfunction "2_2") (pintype "passive"))
    )
    (net (code "11") (name "/col11") (class "Default")
      (node (ref "S211") (pin "2") (pinfunction "2_2") (pintype "passive"))
      (node (ref "S225") (pin "2") (pinfunction "2_2") (pintype "passive"))
      (node (ref "S239") (pin "2") (pinfunction "2_2") (pintype "passive"))
      (node (ref "S253") (pin "2") (pinfunction "2_2") (pintype "passive"))
      (node (ref "S265") (pin "1") (pinfunction "1_1") (pintype "passive"))
      (node (ref "S265_1") (pin "1") (pinfunction "1_1") (pintype "passive"))
    )
    (net (code "12") (name "/col12") (class "Default")
      (node (ref "S212") (pin "2") (pinfunction "2_2") (pintype "passive"))
      (node (ref "S226") (pin "2") (pinfunction "2_2") (pintype "passive"))
      (node (ref "S240") (pin "2") (pinfunction "2_2") (pintype "passive"))
      (node (ref "S241") (pin "1") (pinfunction "1_1") (pintype "passive"))
      (node (ref "S254") (pin "2") (pinfunction "2_2") (pintype "passive"))
    )
    (net (code "13") (name "/col13") (class "Default")
      (node (ref "S213") (pin "2") (pinfunction "2_2") (pintype "passive"))
      (node (ref "S227") (pin "2") (pinfunction "2_2") (pintype "passive"))
      (node (ref "S256") (pin "1") (pinfunction "1_1") (pintype "passive"))
      (node (ref "S256_1") (pin "1") (pinfunction "1_1") (pintype "passive"))
      (node (ref "S266") (pin "2") (pinfunction "2_2") (pintype "passive"))
      (node (ref "S266_1") (pin "2") (pinfunction "2_2") (pintype "passive"))
    )
    (net (code "14") (name "/col14") (class "Default")
      (node (ref "S214") (pin "2") (pinfunction "2_2") (pintype "passive"))
      (node (ref "S228") (pin "2") (pinfunction "2_2") (pintype "passive"))
      (node (ref "S242") (pin "2") (pinfunction "2_2") (pintype "passive"))
      (node (ref "S269") (pin "2") (pinfunction "2_2") (pintype "passive"))
      (node (ref "S300") (pin "2") (pinfunction "2_2") (pintype "passive"))
      (node (ref "S300_1") (pin "2") (pinfunction "2_2") (pintype "passive"))
      (node (ref "S300_2") (pin "2") (pinfunction "2_2") (pintype "passive"))
    )
    (net (code "15") (name "/row1") (class "Default")
      (node (ref "D201") (pin "2") (pinfunction "K_2") (pintype "passive"))
      (node (ref "D202") (pin "2") (pinfunction "K_2") (pintype "passive"))
      (node (ref "D203") (pin "2") (pinfunction "K_2") (pintype "passive"))
      (node (ref "D204") (pin "2") (pinfunction "K_2") (pintype "passive"))
      (node (ref "D205") (pin "2") (pinfunction "K_2") (pintype "passive"))
      (node (ref "D206") (pin "2") (pinfunction "K_2") (pintype "passive"))
      (node (ref "D207") (pin "2") (pinfunction "K_2") (pintype "passive"))
      (node (ref "D208") (pin "2") (pinfunction "K_2") (pintype "passive"))
      (node (ref "D209") (pin "2") (pinfunction "K_2") (pintype "passive"))
      (node (ref "D210") (pin "2") (pinfunction "K_2") (pintype "passive"))
      (node (ref "D211") (pin "2") (pinfunction "K_2") (pintype "passive"))
      (node (ref "D212") (pin "2") (pinfunction "K_2") (pintype "passive"))
      (node (ref "D213") (pin "2") (pinfunction "K_2") (pintype "passive"))
      (node (ref "D214") (pin "2") (pinfunction "K_2") (pintype "passive"))
    )
    (net (code "16") (name "/row2") (class "Default")
      (node (ref "D215") (pin "2") (pinfunction "K_2") (pintype "passive"))
      (node (ref "D216") (pin "2") (pinfunction "K_2") (pintype "passive"))
      (node (ref "D217") (pin "2") (pinfunction "K_2") (pintype "passive"))
      (node (ref "D218") (pin "2") (pinfunction "K_2") (pintype "passive"))
      (node (ref "D219") (pin "2") (pinfunction "K_2") (pintype "passive"))
      (node (ref "D220") (pin "2") (pinfunction "K_2") (pintype "passive"))
      (node (ref "D221") (pin "2") (pinfunction "K_2") (pintype "passive"))
      (node (ref "D222") (pin "2") (pinfunction "K_2") (pintype "passive"))
      (node (ref "D223") (pin "2") (pinfunction "K_2") (pintype "passive"))
      (node (ref "D224") (pin "2") (pinfunction "K_2") (pintype "passive"))
      (node (ref "D225") (pin "2") (pinfunction "K_2") (pintype "passive"))
      (node (ref "D226") (pin "2") (pinfunction "K_2") (pintype "passive"))
      (node (ref "D227") (pin "2") (pinfunction "K_2") (pintype "passive"))
      (node (ref "D228") (pin "2") (pinfunction "K_2") (pintype "passive"))
    )
    (net (code "17") (name "/row3") (class "Default")
      (node (ref "D229") (pin "2") (pinfunction "K_2") (pintype "passive"))
      (node (ref "D230") (pin "2") (pinfunction "K_2") (pintype "passive"))
      (node (ref "D231") (pin "2") (pinfunction "K_2") (pintype "passive"))
      (node (ref "D232") (pin "2") (pinfunction "K_2") (pintype "passive"))
      (node (ref "D233") (pin "2") (pinfunction "K_2") (pintype "passive"))
      (node (ref "D234") (pin "2") (pinfunction "K_2") (pintype "passive"))
      (node (ref "D235") (pin "2") (pinfunction "K_2") (pintype "passive"))
      (node (ref "D236") (pin "2") (pinfunction "K_2") (pintype "passive"))
      (node (ref "D237") (pin "2") (pinfunction "K_2") (pintype "passive"))
      (node (ref "D238") (pin "2") (pinfunction "K_2") (pintype "passive"))
      (node (ref "D239") (pin "2") (pinfunction "K_2") (pintype "passive"))
      (node (ref "D240") (pin "2") (pinfunction "K_2") (pintype "passive"))
      (node (ref "D300") (pin "2") (pinfunction "K_2") (pintype "passive"))
    )
    (net (code "18") (name "/row4") (class "Default")
      (node (ref "D242") (pin "2") (pinfunction "K_2") (pintype "passive"))
      (node (ref "D243") (pin "2") (pinfunction "K_2") (pintype "passive"))
      (node (ref "D244") (pin "2") (pinfunction "K_2") (pintype "passive"))
      (node (ref "D245") (pin "2") (pinfunction "K_2") (pintype "passive"))
      (node (ref "D246") (pin "2") (pinfunction "K_2") (pintype "passive"))
      (node (ref "D247") (pin "2") (pinfunction "K_2") (pintype "passive"))
      (node (ref "D248") (pin "2") (pinfunction "K_2") (pintype "passive"))
      (node (ref "D249") (pin "2") (pinfunction "K_2") (pintype "passive"))
      (node (ref "D250") (pin "2") (pinfunction "K_2") (pintype "passive"))
      (node (ref "D251") (pin "2") (pinfunction "K_2") (pintype "passive"))
      (node (ref "D252") (pin "2") (pinfunction "K_2") (pintype "passive"))
      (node (ref "D253") (pin "2") (pinfunction "K_2") (pintype "passive"))
      (node (ref "D254") (pin "2") (pinfunction "K_2") (pintype "passive"))
      (node (ref "D255") (pin "2") (pinfunction "K_2") (pintype "passive"))
    )
    (net (code "19") (name "/row5") (class "Default")
      (node (ref "D241") (pin "2") (pinfunction "K_2") (pintype "passive"))
      (node (ref "D256") (pin "2") (pinfunction "K_2") (pintype "passive"))
      (node (ref "D257") (pin "2") (pinfunction "K_2") (pintype "passive"))
      (node (ref "D258") (pin "2") (pinfunction "K_2") (pintype "passive"))
      (node (ref "D260") (pin "2") (pinfunction "K_2") (pintype "passive"))
      (node (ref "D261") (pin "2") (pinfunction "K_2") (pintype "passive"))
      (node (ref "D262") (pin "2") (pinfunction "K_2") (pintype "passive"))
      (node (ref "D263") (pin "2") (pinfunction "K_2") (pintype "passive"))
      (node (ref "D264") (pin "2") (pinfunction "K_2") (pintype "passive"))
      (node (ref "D265") (pin "2") (pinfunction "K_2") (pintype "passive"))
      (node (ref "D266") (pin "2") (pinfunction "K_2") (pintype "passive"))
    )
    (net (code "20") (name "Net-(D201-A)") (class "Default")
      (node (ref "D201") (pin "1") (pinfunction "A_1") (pintype "passive"))
      (node (ref "S201") (pin "1") (pinfunction "1_1") (pintype "passive"))
    )
    (net (code "21") (name "Net-(D202-A)") (class "Default")
      (node (ref "D202") (pin "1") (pinfunction "A_1") (pintype "passive"))
      (node (ref "S202") (pin "1") (pinfunction "1_1") (pintype "passive"))
    )
    (net (code "22") (name "Net-(D203-A)") (class "Default")
      (node (ref "D203") (pin "1") (pinfunction "A_1") (pintype "passive"))
      (node (ref "S203") (pin "1") (pinfunction "1_1") (pintype "passive"))
    )
    (net (code "23") (name "Net-(D204-A)") (class "Default")
      (node (ref "D204") (pin "1") (pinfunction "A_1") (pintype "passive"))
      (node (ref "S204") (pin "1") (pinfunction "1_1") (pintype "passive"))
    )
    (net (code "24") (name "Net-(D205-A)") (class "Default")
      (node (ref "D205") (pin "1") (pinfunction "A_1") (pintype "passive"))
      (node (ref "S205") (pin "1") (pinfunction "1_1") (pintype "passive"))
    )
    (net (code "25") (name "Net-(D206-A)") (class "Default")
      (node (ref "D206") (pin "1") (pinfunction "A_1") (pintype "passive"))
      (node (ref "S206") (pin "1") (pinfunction "1_1") (pintype "passive"))
    )
    (net (code "26") (name "Net-(D207-A)") (class "Default")
      (node (ref "D207") (pin "1") (pinfunction "A_1") (pintype "passive"))
      (node (ref "S207") (pin "1") (pinfunction "1_1") (pintype "passive"))
    )
    (net (code "27") (name "Net-(D208-A)") (class "Default")
      (node (ref "D208") (pin "1") (pinfunction "A_1") (pintype "passive"))
      (node (ref "S208") (pin "1") (pinfunction "1_1") (pintype "passive"))
    )
    (net (code "28") (name "Net-(D209-A)") (class "Default")
      (node (ref "D209") (pin "1") (pinfunction "A_1") (pintype "passive"))
      (node (ref "S209") (pin "1") (pinfunction "1_1") (pintype "passive"))
    )
    (net (code "29") (name "Net-(D210-A)") (class "Default")
      (node (ref "D210") (pin "1") (pinfunction "A_1") (pintype "passive"))
      (node (ref "S210") (pin "1") (pinfunction "1_1") (pintype "passive"))
    )
    (net (code "30") (name "Net-(D211-A)") (class "Default")
      (node (ref "D211") (pin "1") (pinfunction "A_1") (pintype "passive"))
      (node (ref "S211") (pin "1") (pinfunction "1_1") (pintype "passive"))
    )
    (net (code "31") (name "Net-(D212-A)") (class "Default")
      (node (ref "D212") (pin "1") (pinfunction "A_1") (pintype "passive"))
      (node (ref "S212") (pin "1") (pinfunction "1_1") (pintype "passive"))
    )
    (net (code "32") (name "Net-(D213-A)") (class "Default")
      (node (ref "D213") (pin "1") (pinfunction "A_1") (pintype "passive"))
      (node (ref "S213") (pin "1") (pinfunction "1_1") (pintype "passive"))
    )
    (net (code "33") (name "Net-(D214-A)") (class "Default")
      (node (ref "D214") (pin "1") (pinfunction "A_1") (pintype "passive"))
      (node (ref "S214") (pin "1") (pinfunction "1_1") (pintype "passive"))
    )
    (net (code "34") (name "Net-(D215-A)") (class "Default")
      (node (ref "D215") (pin "1") (pinfunction "A_1") (pintype "passive"))
      (node (ref "S215") (pin "1") (pinfunction "1_1") (pintype "passive"))
    )
    (net (code "35") (name "Net-(D216-A)") (class "Default")
      (node (ref "D216") (pin "1") (pinfunction "A_1") (pintype "passive"))
      (node (ref "S216") (pin "1") (pinfunction "1_1") (pintype "passive"))
    )
    (net (code "36") (name "Net-(D217-A)") (class "Default")
      (node (ref "D217") (pin "1") (pinfunction "A_1") (pintype "passive"))
      (node (ref "S217") (pin "1") (pinfunction "1_1") (pintype "passive"))
    )
    (net (code "37") (name "Net-(D218-A)") (class "Default")
      (node (ref "D218") (pin "1") (pinfunction "A_1") (pintype "passive"))
      (node (ref "S218") (pin "1") (pinfunction "1_1") (pintype "passive"))
    )
    (net (code "38") (name "Net-(D219-A)") (class "Default")
      (node (ref "D219") (pin "1") (pinfunction "A_1") (pintype "passive"))
      (node (ref "S219") (pin "1") (pinfunction "1_1") (pintype "passive"))
    )
    (net (code "39") (name "Net-(D220-A)") (class "Default")
      (node (ref "D220") (pin "1") (pinfunction "A_1") (pintype "passive"))
      (node (ref "S220") (pin "1") (pinfunction "1_1") (pintype "passive"))
    )
    (net (code "40") (name "Net-(D221-A)") (class "Default")
      (node (ref "D221") (pin "1") (pinfunction "A_1") (pintype "passive"))
      (node (ref "S221") (pin "1") (pinfunction "1_1") (pintype "passive"))
    )
    (net (code "41") (name "Net-(D222-A)") (class "Default")
      (node (ref "D222") (pin "1") (pinfunction "A_1") (pintype "passive"))
      (node (ref "S222") (pin "1") (pinfunction "1_1") (pintype "passive"))
    )
    (net (code "42") (name "Net-(D223-A)") (class "Default")
      (node (ref "D223") (pin "1") (pinfunction "A_1") (pintype "passive"))
      (node (ref "S223") (pin "1") (pinfunction "1_1") (pintype "passive"))
    )
    (net (code "43") (name "Net-(D224-A)") (class "Default")
      (node (ref "D224") (pin "1") (pinfunction "A_1") (pintype "passive"))
      (node (ref "S224") (pin "1") (pinfunction "1_1") (pintype "passive"))
    )
    (net (code "44") (name "Net-(D225-A)") (class "Default")
      (node (ref "D225") (pin "1") (pinfunction "A_1") (pintype "passive"))
      (node (ref "S225") (pin "1") (pinfunction "1_1") (pintype "passive"))
    )
    (net (code "45") (name "Net-(D226-A)") (class "Default")
      (node (ref "D226") (pin "1") (pinfunction "A_1") (pintype "passive"))
      (node (ref "S226") (pin "1") (pinfunction "1_1") (pintype "passive"))
    )
    (net (code "46") (name "Net-(D227-A)") (class "Default")
      (node (ref "D227") (pin "1") (pinfunction "A_1") (pintype "passive"))
      (node (ref "S227") (pin "1") (pinfunction "1_1") (pintype "passive"))
    )
    (net (code "47") (name "Net-(D228-A)") (class "Default")
      (node (ref "D228") (pin "1") (pinfunction "A_1") (pintype "passive"))
      (node (ref "S228") (pin "1") (pinfunction "1_1") (pintype "passive"))
    )
    (net (code "48") (name "Net-(D229-A)") (class "Default")
      (node (ref "D229") (pin "1") (pinfunction "A_1") (pintype "passive"))
      (node (ref "S229") (pin "1") (pinfunction "1_1") (pintype "passive"))
    )
    (net (code "49") (name "Net-(D230-A)") (class "Default")
      (node (ref "D230") (pin "1") (pinfunction "A_1") (pintype "passive"))
      (node (ref "S230") (pin "1") (pinfunction "1_1") (pintype "passive"))
    )
    (net (code "50") (name "Net-(D231-A)") (class "Default")
      (node (ref "D231") (pin "1") (pinfunction "A_1") (pintype "passive"))
      (node (ref "S231") (pin "1") (pinfunction "1_1") (pintype "passive"))
    )
    (net (code "51") (name "Net-(D232-A)") (class "Default")
      (node (ref "D232") (pin "1") (pinfunction "A_1") (pintype "passive"))
      (node (ref "S232") (pin "1") (pinfunction "1_1") (pintype "passive"))
    )
    (net (code "52") (name "Net-(D233-A)") (class "Default")
      (node (ref "D233") (pin "1") (pinfunction "A_1") (pintype "passive"))
      (node (ref "S233") (pin "1") (pinfunction "1_1") (pintype "passive"))
    )
    (net (code "53") (name "Net-(D234-A)") (class "Default")
      (node (ref "D234") (pin "1") (pinfunction "A_1") (pintype "passive"))
      (node (ref "S234") (pin "1") (pinfunction "1_1") (pintype "passive"))
    )
    (net (code "54") (name "Net-(D235-A)") (class "Default")
      (node (ref "D235") (pin "1") (pinfunction "A_1") (pintype "passive"))
      (node (ref "S235") (pin "1") (pinfunction "1_1") (pintype "passive"))
    )
    (net (code "55") (name "Net-(D236-A)") (class "Default")
      (node (ref "D236") (pin "1") (pinfunction "A_1") (pintype "passive"))
      (node (ref "S236") (pin "1") (pinfunction "1_1") (pintype "passive"))
    )
    (net (code "56") (name "Net-(D237-A)") (class "Default")
      (node (ref "D237") (pin "1") (pinfunction "A_1") (pintype "passive"))
      (node (ref "S237") (pin "1") (pinfunction "1_1") (pintype "passive"))
    )
    (net (code "57") (name "Net-(D238-A)") (class "Default")
      (node (ref "D238") (pin "1") (pinfunction "A_1") (pintype "passive"))
      (node (ref "S238") (pin "1") (pinfunction "1_1") (pintype "passive"))
    )
    (net (code "58") (name "Net-(D239-A)") (class "Default")
      (node (ref "D239") (pin "1") (pinfunction "A_1") (pintype "passive"))
      (node (ref "S239") (pin "1") (pinfunction "1_1") (pintype "passive"))
    )
    (net (code "59") (name "Net-(D240-A)") (class "Default")
      (node (ref "D240") (pin "1") (pinfunction "A_1") (pintype "passive"))
      (node (ref "S240") (pin "1") (pinfunction "1_1") (pintype "passive"))
    )
    (net (code "60") (name "Net-(D241-A)") (class "Default")
      (node (ref "D241") (pin "1") (pinfunction "A_1") (pintype "passive"))
      (node (ref "S241") (pin "2") (pinfunction "2_2") (pintype "passive"))
    )
    (net (code "61") (name "Net-(D242-A)") (class "Default")
      (node (ref "D242") (pin "1") (pinfunction "A_1") (pintype "passive"))
      (node (ref "S242") (pin "1") (pinfunction "1_1") (pintype "passive"))
    )
    (net (code "62") (name "Net-(D243-A)") (class "Default")
      (node (ref "D243") (pin "1") (pinfunction "A_1") (pintype "passive"))
      (node (ref "S243") (pin "1") (pinfunction "1_1") (pintype "passive"))
    )
    (net (code "63") (name "Net-(D244-A)") (class "Default")
      (node (ref "D244") (pin "1") (pinfunction "A_1") (pintype "passive"))
      (node (ref "S244") (pin "2") (pinfunction "2_2") (pintype "passive"))
    )
    (net (code "64") (name "Net-(D245-A)") (class "Default")
      (node (ref "D245") (pin "1") (pinfunction "A_1") (pintype "passive"))
      (node (ref "S245") (pin "1") (pinfunction "1_1") (pintype "passive"))
    )
    (net (code "65") (name "Net-(D246-A)") (class "Default")
      (node (ref "D246") (pin "1") (pinfunction "A_1") (pintype "passive"))
      (node (ref "S246") (pin "1") (pinfunction "1_1") (pintype "passive"))
    )
    (net (code "66") (name "Net-(D247-A)") (class "Default")
      (node (ref "D247") (pin "1") (pinfunction "A_1") (pintype "passive"))
      (node (ref "S247") (pin "1") (pinfunction "1_1") (pintype "passive"))
    )
    (net (code "67") (name "Net-(D248-A)") (class "Default")
      (node (ref "D248") (pin "1") (pinfunction "A_1") (pintype "passive"))
      (node (ref "S248") (pin "1") (pinfunction "1_1") (pintype "passive"))
    )
    (net (code "68") (name "Net-(D249-A)") (class "Default")
      (node (ref "D249") (pin "1") (pinfunction "A_1") (pintype "passive"))
      (node (ref "S249") (pin "1") (pinfunction "1_1") (pintype "passive"))
    )
    (net (code "69") (name "Net-(D250-A)") (class "Default")
      (node (ref "D250") (pin "1") (pinfunction "A_1") (pintype "passive"))
      (node (ref "S250") (pin "1") (pinfunction "1_1") (pintype "passive"))
    )
    (net (code "70") (name "Net-(D251-A)") (class "Default")
      (node (ref "D251") (pin "1") (pinfunction "A_1") (pintype "passive"))
      (node (ref "S251") (pin "1") (pinfunction "1_1") (pintype "passive"))
    )
    (net (code "71") (name "Net-(D252-A)") (class "Default")
      (node (ref "D252") (pin "1") (pinfunction "A_1") (pintype "passive"))
      (node (ref "S252") (pin "1") (pinfunction "1_1") (pintype "passive"))
    )
    (net (code "72") (name "Net-(D253-A)") (class "Default")
      (node (ref "D253") (pin "1") (pinfunction "A_1") (pintype "passive"))
      (node (ref "S253") (pin "1") (pinfunction "1_1") (pintype "passive"))
    )
    (net (code "73") (name "Net-(D254-A)") (class "Default")
      (node (ref "D254") (pin "1") (pinfunction "A_1") (pintype "passive"))
      (node (ref "S254") (pin "1") (pinfunction "1_1") (pintype "passive"))
    )
    (net (code "74") (name "Net-(D255-A)") (class "Default")
      (node (ref "D255") (pin "1") (pinfunction "A_1") (pintype "passive"))
      (node (ref "S256") (pin "2") (pinfunction "2_2") (pintype "passive"))
      (node (ref "S256_1") (pin "2") (pinfunction "2_2") (pintype "passive"))
    )
    (net (code "75") (name "Net-(D256-A)") (class "Default")
      (node (ref "D256") (pin "1") (pinfunction "A_1") (pintype "passive"))
      (node (ref "S269") (pin "1") (pinfunction "1_1") (pintype "passive"))
    )
    (net (code "76") (name "Net-(D257-A)") (class "Default")
      (node (ref "D257") (pin "1") (pinfunction "A_1") (pintype "passive"))
      (node (ref "S257") (pin "2") (pinfunction "2_2") (pintype "passive"))
      (node (ref "S257_1") (pin "2") (pinfunction "2_2") (pintype "passive"))
      (node (ref "S257_2") (pin "2") (pinfunction "2_2") (pintype "passive"))
    )
    (net (code "77") (name "Net-(D258-A)") (class "Default")
      (node (ref "D258") (pin "1") (pinfunction "A_1") (pintype "passive"))
      (node (ref "S258") (pin "1") (pinfunction "1_1") (pintype "passive"))
    )
    (net (code "78") (name "Net-(D260-A)") (class "Default")
      (node (ref "D260") (pin "1") (pinfunction "A_1") (pintype "passive"))
      (node (ref "S260") (pin "1") (pinfunction "1_1") (pintype "passive"))
      (node (ref "S260_1") (pin "1") (pinfunction "1_1") (pintype "passive"))
      (node (ref "S260_2") (pin "1") (pinfunction "1_1") (pintype "passive"))
      (node (ref "S260_3") (pin "1") (pinfunction "1_1") (pintype "passive"))
    )
    (net (code "79") (name "Net-(D261-A)") (class "Default")
      (node (ref "D261") (pin "1") (pinfunction "A_1") (pintype "passive"))
      (node (ref "S261") (pin "1") (pinfunction "1_1") (pintype "passive"))
      (node (ref "S261_1") (pin "1") (pinfunction "1_1") (pintype "passive"))
      (node (ref "S261_2") (pin "1") (pinfunction "1_1") (pintype "passive"))
    )
    (net (code "80") (name "Net-(D262-A)") (class "Default")
      (node (ref "D262") (pin "1") (pinfunction "A_1") (pintype "passive"))
      (node (ref "S262") (pin "2") (pinfunction "2_2") (pintype "passive"))
      (node (ref "S262_1") (pin "2") (pinfunction "2_2") (pintype "passive"))
      (node (ref "S262_2") (pin "2") (pinfunction "2_2") (pintype "passive"))
      (node (ref "S262_3") (pin "2") (pinfunction "2_2") (pintype "passive"))
    )
    (net (code "81") (name "Net-(D263-A)") (class "Default")
      (node (ref "D263") (pin "1") (pinfunction "A_1") (pintype "passive"))
      (node (ref "S263") (pin "2") (pinfunction "2_2") (pintype "passive"))
    )
    (net (code "82") (name "Net-(D264-A)") (class "Default")
      (node (ref "D264") (pin "1") (pinfunction "A_1") (pintype "passive"))
      (node (ref "S264") (pin "1") (pinfunction "1_1") (pintype "passive"))
      (node (ref "S264_1") (pin "1") (pinfunction "1_1") (pintype "passive"))
    )
    (net (code "83") (name "Net-(D265-A)") (class "Default")
      (node (ref "D265") (pin "1") (pinfunction "A_1") (pintype "passive"))
      (node (ref "S265") (pin "2") (pinfunction "2_2") (pintype "passive"))
      (node (ref "S265_1") (pin "2") (pinfunction "2_2") (pintype "passive"))
    )
    (net (code "84") (name "Net-(D266-A)") (class "Default")
      (node (ref "D266") (pin "1") (pinfunction "A_1") (pintype "passive"))
      (node (ref "S266") (pin "1") (pinfunction "1_1") (pintype "passive"))
      (node (ref "S266_1") (pin "1") (pinfunction "1_1") (pintype "passive"))
    )
    (net (code "85") (name "Net-(D300-A)") (class "Default")
      (node (ref "D300") (pin "1") (pinfunction "A_1") (pintype "passive"))
      (node (ref "S300") (pin "1") (pinfunction "1_1") (pintype "passive"))
      (node (ref "S300_1") (pin "1") (pinfunction "1_1") (pintype "passive"))
      (node (ref "S300_2") (pin "1") (pinfunction "1_1") (pintype "passive"))
    )
  )
)
